# POWER_CON.net
KiCad netlist of a schematic drawn in Altium Designer
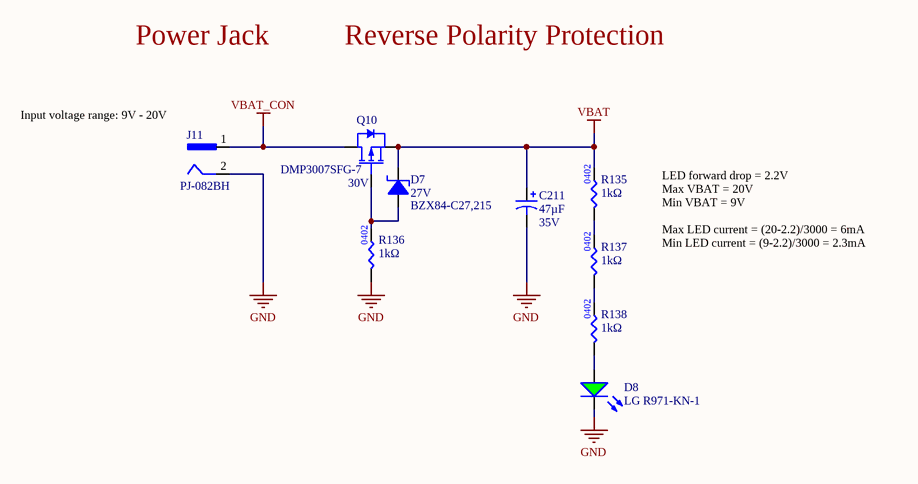
[diagram p0: POWER CON.SchDoc]

(export (version "E")
  (design (tool "Eeschema 10.0.6"))
  (components
    (comp (ref "C211")
      (value "47µF")
      (footprint "RADIAL_CORNELL_D")
      (description "CAP ALUM POLY HYB 47UF 35V SMD")
      (fields (field (name "VOLTAGE RATING") "35V") (field (name "Comment") "CAP_47uF_35V_ALUM"))
      (libsource (lib "UWRT_Schematic_Library_2020") (part "CAP_47uF_35V_ALUM"))
    )
    (comp (ref "D7")
      (value "DIO_ZENER_27V")
      (footprint "SOT23-3")
      (description "DIODE ZENER 27V 250MW SOT23")
      (fields
        (field (name "MANUFACTURER PART NUMBER 1") "BZX84-C27,215")
        (field (name "WORKING VOLTAGE") "27V")
      )
      (libsource (lib "UWRT_Schematic_Library_2020") (part "DIO_ZENER_27V"))
    )
    (comp (ref "D8")
      (value "DIO_LED_G")
      (footprint "LED_0805_GREEN")
      (description "LED GREEN DIFFUSED 0805 SMD")
      (fields (field (name "MANUFACTURER PART NUMBER 1") "LG R971-KN-1"))
      (libsource (lib "UWRT_Schematic_Library_2020") (part "DIO_LED_G"))
    )
    (comp (ref "J11")
      (value "CON_POWER_JACK")
      (footprint "SnapEDApcb:CUI_PJ-082BH")
      (description "2.5 x 6.5 mm, 10.0 A, Horizontal, Through Hole, Shielded, Dc Power Jack Connector")
      (fields (field (name "MANUFACTURER PART NUMBER 1") "PJ-082BH"))
      (libsource (lib "UWRT_Schematic_Library_2020") (part "CON_POWER_JACK"))
    )
    (comp (ref "Q10")
      (value "PMOS_30V_70A")
      (footprint "DMP3007SFG-7")
      (description "MOSFET P-CH 30V 70A POWERDI3333")
      (fields (field (name "MANUFACTURER PART NUMBER 1") "DMP3007SFG-7") (field (name "VDSS") "30V"))
      (libsource (lib "UWRT_Schematic_Library_2020") (part "PMOS_30V_70A"))
    )
    (comp (ref "R135")
      (value "RES_1kΩ_0402")
      (footprint "RES0402")
      (fields
        (field (name "MANUFACTURER") "Stackpole Electronics")
        (field (name "MANUFACTURER PART NUMBER") "RMCF0402FT1K00")
        (field (name "TOLERANCE") "1%")
        (field (name "RESISTANCE") "1kΩ")
      )
      (libsource (lib "UWRT_Schematic_Library_2020") (part "RES_1kΩ_0402"))
    )
    (comp (ref "R136")
      (value "RES_1kΩ_0402")
      (footprint "RES0402")
      (fields
        (field (name "MANUFACTURER") "Stackpole Electronics")
        (field (name "MANUFACTURER PART NUMBER") "RMCF0402FT1K00")
        (field (name "TOLERANCE") "1%")
        (field (name "RESISTANCE") "1kΩ")
      )
      (libsource (lib "UWRT_Schematic_Library_2020") (part "RES_1kΩ_0402"))
    )
    (comp (ref "R137")
      (value "RES_1kΩ_0402")
      (footprint "RES0402")
      (fields
        (field (name "MANUFACTURER") "Stackpole Electronics")
        (field (name "MANUFACTURER PART NUMBER") "RMCF0402FT1K00")
        (field (name "TOLERANCE") "1%")
        (field (name "RESISTANCE") "1kΩ")
      )
      (libsource (lib "UWRT_Schematic_Library_2020") (part "RES_1kΩ_0402"))
    )
    (comp (ref "R138")
      (value "RES_1kΩ_0402")
      (footprint "RES0402")
      (fields
        (field (name "MANUFACTURER") "Stackpole Electronics")
        (field (name "MANUFACTURER PART NUMBER") "RMCF0402FT1K00")
        (field (name "TOLERANCE") "1%")
        (field (name "RESISTANCE") "1kΩ")
      )
      (libsource (lib "UWRT_Schematic_Library_2020") (part "RES_1kΩ_0402"))
    )
  )
  (nets
    (net (code "1") (name "GND") (class "Default")
      (node (ref "C211") (pin "2") (pinfunction "2_2") (pintype "passive"))
      (node (ref "D8") (pin "2") (pinfunction "K_2") (pintype "passive"))
      (node (ref "J11") (pin "2") (pinfunction "2_2") (pintype "passive"))
      (node (ref "R136") (pin "1") (pinfunction "1_1") (pintype "passive"))
    )
    (net (code "2") (name "Net-(D7-Anode)") (class "Default")
      (node (ref "D7") (pin "1") (pinfunction "Anode_1") (pintype "passive"))
      (node (ref "Q10") (pin "2") (pinfunction "Gate_2") (pintype "passive"))
      (node (ref "R136") (pin "2") (pinfunction "2_2") (pintype "passive"))
    )
    (net (code "3") (name "Net-(D8-A)") (class "Default")
      (node (ref "D8") (pin "1") (pinfunction "A_1") (pintype "passive"))
      (node (ref "R138") (pin "1") (pinfunction "1_1") (pintype "passive"))
    )
    (net (code "4") (name "Net-(R135-Pad1)") (class "Default")
      (node (ref "R135") (pin "1") (pinfunction "1_1") (pintype "passive"))
      (node (ref "R137") (pin "2") (pinfunction "2_2") (pintype "passive"))
    )
    (net (code "5") (name "Net-(R137-Pad1)") (class "Default")
      (node (ref "R137") (pin "1") (pinfunction "1_1") (pintype "passive"))
      (node (ref "R138") (pin "2") (pinfunction "2_2") (pintype "passive"))
    )
    (net (code "6") (name "VBAT") (class "Default")
      (node (ref "C211") (pin "1") (pinfunction "1_1") (pintype "passive"))
      (node (ref "D7") (pin "2") (pinfunction "Cathode_2") (pintype "passive"))
      (node (ref "Q10") (pin "3") (pinfunction "Source_3") (pintype "passive"))
      (node (ref "R135") (pin "2") (pinfunction "2_2") (pintype "passive"))
    )
    (net (code "7") (name "VBAT_CON") (class "Default")
      (node (ref "J11") (pin "1") (pinfunction "1_1") (pintype "passive"))
      (node (ref "Q10") (pin "1") (pinfunction "Drain_1") (pintype "passive"))
    )
  )
)
